# MC_BX1.net
KiCad netlist of a schematic drawn in EAGLE
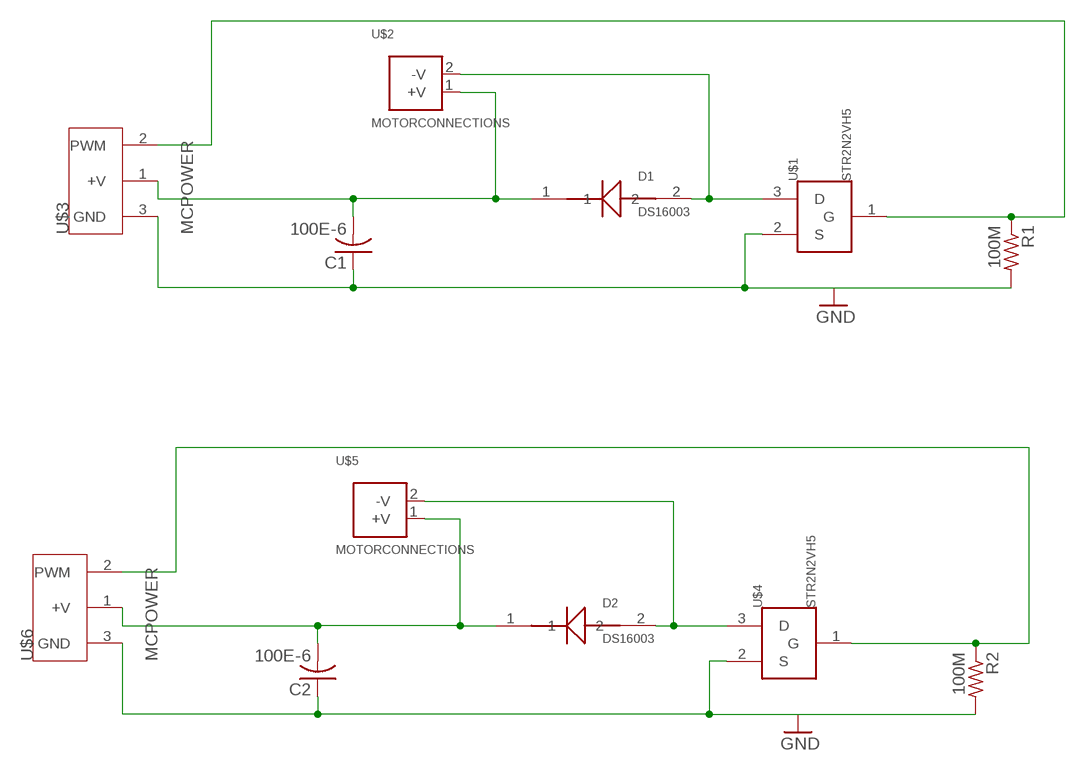
[diagram p0: schematic, sheet 1]

(export (version "E")
  (design (tool "Eeschema 10.0.6"))
  (components
    (comp (ref "C1")
      (value "100E-6")
      (footprint "eagle-import:C0805")
      (libsource (lib "eagle-import") (part "C-USC0805"))
    )
    (comp (ref "C2")
      (value "100E-6")
      (footprint "eagle-import:C0805")
      (libsource (lib "eagle-import") (part "C-USC0805"))
    )
    (comp (ref "D1")
      (value "DS16003")
      (footprint "eagle-import:DS16003_F")
      (libsource (lib "eagle-import") (part "DS16003"))
    )
    (comp (ref "D2")
      (value "DS16003")
      (footprint "eagle-import:DS16003_F")
      (libsource (lib "eagle-import") (part "DS16003"))
    )
    (comp (ref "R1")
      (value "100M")
      (footprint "eagle-import:R0805")
      (libsource (lib "eagle-import") (part "R-US_R0805"))
    )
    (comp (ref "R2")
      (value "100M")
      (footprint "eagle-import:R0805")
      (libsource (lib "eagle-import") (part "R-US_R0805"))
    )
    (comp (ref "U$1")
      (value "STR2N2VH5")
      (footprint "eagle-import:T-STR2N2VH5_F")
      (libsource (lib "eagle-import") (part "STR2N2VH5"))
    )
    (comp (ref "U$2")
      (value "MOTORCONNECTIONS")
      (footprint "eagle-import:MOTORCONNECTIONS")
      (libsource (lib "eagle-import") (part "MOTORCONNECTIONS"))
    )
    (comp (ref "U$3")
      (value "MCPOWER")
      (footprint "eagle-import:MCPOWER")
      (libsource (lib "eagle-import") (part "MCPOWER"))
    )
    (comp (ref "U$4")
      (value "STR2N2VH5")
      (footprint "eagle-import:T-STR2N2VH5_F")
      (libsource (lib "eagle-import") (part "STR2N2VH5"))
    )
    (comp (ref "U$5")
      (value "MOTORCONNECTIONS")
      (footprint "eagle-import:MOTORCONNECTIONS")
      (libsource (lib "eagle-import") (part "MOTORCONNECTIONS"))
    )
    (comp (ref "U$6")
      (value "MCPOWER")
      (footprint "eagle-import:MCPOWER")
      (libsource (lib "eagle-import") (part "MCPOWER"))
    )
  )
  (nets
    (net (code "1") (name "GND") (class "Default")
      (node (ref "C1") (pin "1") (pinfunction "1_1") (pintype "passive"))
      (node (ref "C2") (pin "1") (pinfunction "1_1") (pintype "passive"))
      (node (ref "R1") (pin "2") (pinfunction "2_2") (pintype "passive"))
      (node (ref "R2") (pin "2") (pinfunction "2_2") (pintype "passive"))
      (node (ref "U$1") (pin "2") (pinfunction "S_2") (pintype "bidirectional"))
      (node (ref "U$3") (pin "3") (pinfunction "GND_3") (pintype "bidirectional"))
      (node (ref "U$4") (pin "2") (pinfunction "S_2") (pintype "bidirectional"))
      (node (ref "U$6") (pin "3") (pinfunction "GND_3") (pintype "bidirectional"))
    )
    (net (code "2") (name "Net-(U$1-D)") (class "Default")
      (node (ref "D1") (pin "2") (pinfunction "2_2") (pintype "bidirectional"))
      (node (ref "U$1") (pin "3") (pinfunction "D_3") (pintype "bidirectional"))
      (node (ref "U$2") (pin "2") (pinfunction "-V_2") (pintype "bidirectional"))
    )
    (net (code "3") (name "Net-(U$1-G)") (class "Default")
      (node (ref "R1") (pin "1") (pinfunction "1_1") (pintype "passive"))
      (node (ref "U$1") (pin "1") (pinfunction "G_1") (pintype "bidirectional"))
      (node (ref "U$3") (pin "2") (pinfunction "PWM_2") (pintype "bidirectional"))
    )
    (net (code "4") (name "Net-(U$2-+V)") (class "Default")
      (node (ref "C1") (pin "2") (pinfunction "2_2") (pintype "passive"))
      (node (ref "D1") (pin "1") (pinfunction "1_1") (pintype "bidirectional"))
      (node (ref "U$2") (pin "1") (pinfunction "+V_1") (pintype "bidirectional"))
      (node (ref "U$3") (pin "1") (pinfunction "+V_1") (pintype "bidirectional"))
    )
    (net (code "5") (name "Net-(U$4-D)") (class "Default")
      (node (ref "D2") (pin "2") (pinfunction "2_2") (pintype "bidirectional"))
      (node (ref "U$4") (pin "3") (pinfunction "D_3") (pintype "bidirectional"))
      (node (ref "U$5") (pin "2") (pinfunction "-V_2") (pintype "bidirectional"))
    )
    (net (code "6") (name "Net-(U$4-G)") (class "Default")
      (node (ref "R2") (pin "1") (pinfunction "1_1") (pintype "passive"))
      (node (ref "U$4") (pin "1") (pinfunction "G_1") (pintype "bidirectional"))
      (node (ref "U$6") (pin "2") (pinfunction "PWM_2") (pintype "bidirectional"))
    )
    (net (code "7") (name "Net-(U$5-+V)") (class "Default")
      (node (ref "C2") (pin "2") (pinfunction "2_2") (pintype "passive"))
      (node (ref "D2") (pin "1") (pinfunction "1_1") (pintype "bidirectional"))
      (node (ref "U$5") (pin "1") (pinfunction "+V_1") (pintype "bidirectional"))
      (node (ref "U$6") (pin "1") (pinfunction "+V_1") (pintype "bidirectional"))
    )
  )
)
